# Oraculo_V2.net
KiCad netlist of a schematic drawn in EAGLE
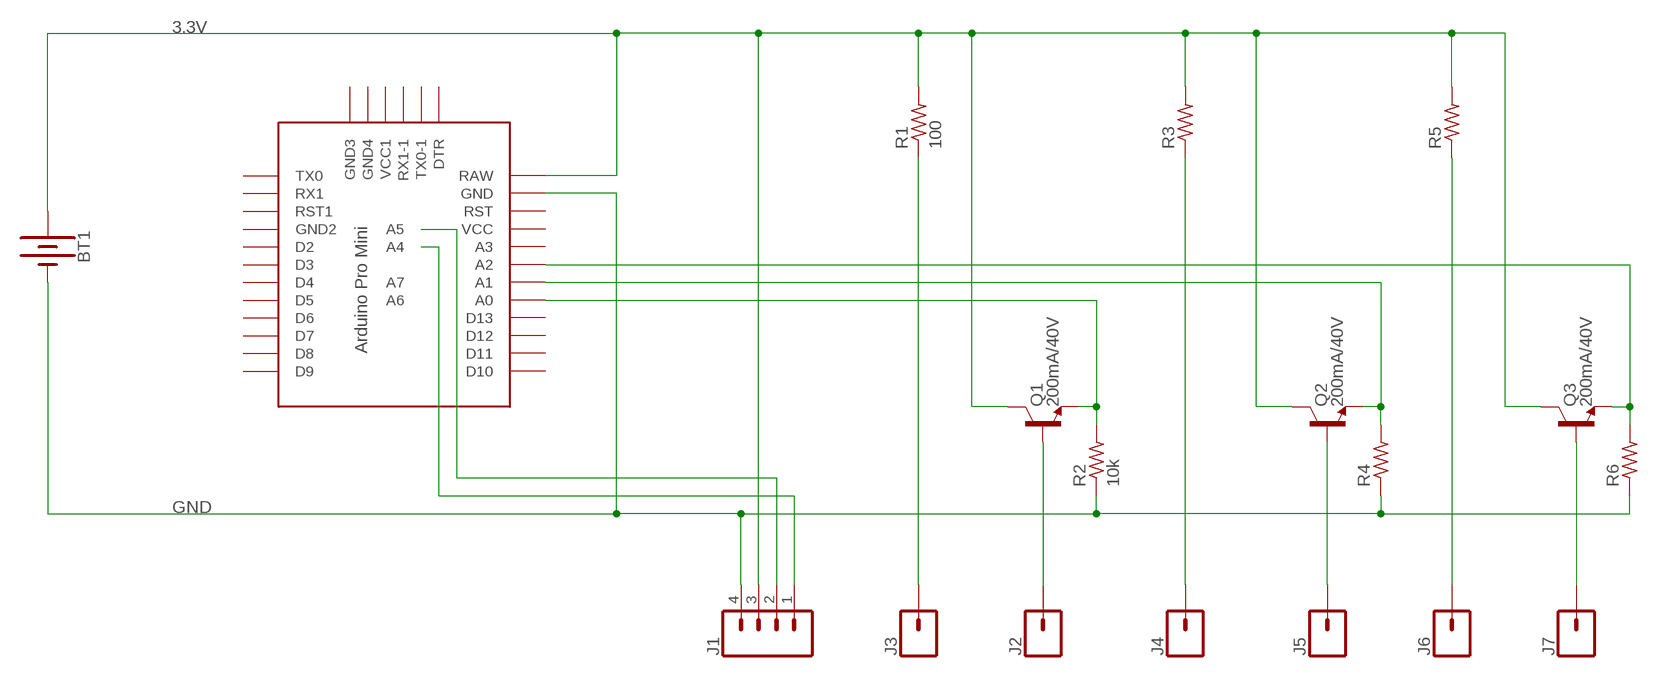
[diagram p0: schematic, sheet 1]

(export (version "E")
  (design (tool "Eeschema 10.0.6"))
  (components
    (comp (ref "BT1")
      (value "BATTERY-20MM_PTH")
      (footprint "eagle-import:BATTCOM_20MM_PTH")
      (libsource (lib "eagle-import") (part "BATTERY-20MM_PTH"))
    )
    (comp (ref "J1")
      (value "CONN_04")
      (footprint "eagle-import:1X04")
      (libsource (lib "eagle-import") (part "CONN_04"))
    )
    (comp (ref "J2")
      (value "CONN_01PTH_2MM")
      (footprint "eagle-import:1X01_2MM")
      (libsource (lib "eagle-import") (part "CONN_01PTH_2MM"))
    )
    (comp (ref "J3")
      (value "CONN_01PTH_2MM")
      (footprint "eagle-import:1X01_2MM")
      (libsource (lib "eagle-import") (part "CONN_01PTH_2MM"))
    )
    (comp (ref "J4")
      (value "CONN_01PTH_2MM")
      (footprint "eagle-import:1X01_2MM")
      (libsource (lib "eagle-import") (part "CONN_01PTH_2MM"))
    )
    (comp (ref "J5")
      (value "CONN_01PTH_2MM")
      (footprint "eagle-import:1X01_2MM")
      (libsource (lib "eagle-import") (part "CONN_01PTH_2MM"))
    )
    (comp (ref "J6")
      (value "CONN_01PTH_2MM")
      (footprint "eagle-import:1X01_2MM")
      (libsource (lib "eagle-import") (part "CONN_01PTH_2MM"))
    )
    (comp (ref "J7")
      (value "CONN_01PTH_2MM")
      (footprint "eagle-import:1X01_2MM")
      (libsource (lib "eagle-import") (part "CONN_01PTH_2MM"))
    )
    (comp (ref "Q1")
      (value "200mA/40V")
      (footprint "eagle-import:TO-92")
      (libsource (lib "eagle-import") (part "TRANS_NPN-2N3904"))
    )
    (comp (ref "Q2")
      (value "200mA/40V")
      (footprint "eagle-import:TO-92")
      (libsource (lib "eagle-import") (part "TRANS_NPN-2N3904"))
    )
    (comp (ref "Q3")
      (value "200mA/40V")
      (footprint "eagle-import:TO-92")
      (libsource (lib "eagle-import") (part "TRANS_NPN-2N3904"))
    )
    (comp (ref "R1")
      (value "100")
      (footprint "eagle-import:0204_7")
      (libsource (lib "eagle-import") (part "R-US_0204/7"))
    )
    (comp (ref "R2")
      (value "10k")
      (footprint "eagle-import:0204_7")
      (libsource (lib "eagle-import") (part "R-US_0204/7"))
    )
    (comp (ref "R3")
      (value "R-US_0204/7")
      (footprint "eagle-import:0204_7")
      (libsource (lib "eagle-import") (part "R-US_0204/7"))
    )
    (comp (ref "R4")
      (value "R-US_0204/7")
      (footprint "eagle-import:0204_7")
      (libsource (lib "eagle-import") (part "R-US_0204/7"))
    )
    (comp (ref "R5")
      (value "R-US_0204/7")
      (footprint "eagle-import:0204_7")
      (libsource (lib "eagle-import") (part "R-US_0204/7"))
    )
    (comp (ref "R6")
      (value "R-US_0204/7")
      (footprint "eagle-import:0204_7")
      (libsource (lib "eagle-import") (part "R-US_0204/7"))
    )
    (comp (ref "U$1")
      (value "PRO-MINI-2")
      (footprint "eagle-import:PRO-MINI-2")
      (libsource (lib "eagle-import") (part "PRO-MINI-2"))
    )
  )
  (nets
    (net (code "1") (name "/3.3V") (class "Default")
      (node (ref "BT1") (pin "1") (pinfunction "+_1") (pintype "power_in"))
      (node (ref "J1") (pin "3") (pinfunction "3_3") (pintype "passive"))
      (node (ref "Q1") (pin "3") (pinfunction "C_3") (pintype "passive"))
      (node (ref "Q2") (pin "3") (pinfunction "C_3") (pintype "passive"))
      (node (ref "Q3") (pin "3") (pinfunction "C_3") (pintype "passive"))
      (node (ref "R1") (pin "2") (pinfunction "2_2") (pintype "passive"))
      (node (ref "R3") (pin "2") (pinfunction "2_2") (pintype "passive"))
      (node (ref "R5") (pin "2") (pinfunction "2_2") (pintype "passive"))
      (node (ref "U$1") (pin "RAW") (pinfunction "RAW_RAW") (pintype "bidirectional"))
    )
    (net (code "2") (name "/GND") (class "Default")
      (node (ref "BT1") (pin "2") (pinfunction "-_2") (pintype "power_in"))
      (node (ref "J1") (pin "4") (pinfunction "4_4") (pintype "passive"))
      (node (ref "R2") (pin "1") (pinfunction "1_1") (pintype "passive"))
      (node (ref "R4") (pin "1") (pinfunction "1_1") (pintype "passive"))
      (node (ref "R6") (pin "1") (pinfunction "1_1") (pintype "passive"))
      (node (ref "U$1") (pin "GND") (pinfunction "GND_GND") (pintype "bidirectional"))
    )
    (net (code "3") (name "Net-(J1-Pad1)") (class "Default")
      (node (ref "J1") (pin "1") (pinfunction "1_1") (pintype "passive"))
      (node (ref "U$1") (pin "A4") (pinfunction "A4_A4") (pintype "bidirectional"))
    )
    (net (code "4") (name "Net-(J1-Pad2)") (class "Default")
      (node (ref "J1") (pin "2") (pinfunction "2_2") (pintype "passive"))
      (node (ref "U$1") (pin "A5") (pinfunction "A5_A5") (pintype "bidirectional"))
    )
    (net (code "5") (name "Net-(J3-Pad1)") (class "Default")
      (node (ref "J3") (pin "1") (pinfunction "1_1") (pintype "passive"))
      (node (ref "R1") (pin "1") (pinfunction "1_1") (pintype "passive"))
    )
    (net (code "6") (name "Net-(J4-Pad1)") (class "Default")
      (node (ref "J4") (pin "1") (pinfunction "1_1") (pintype "passive"))
      (node (ref "R3") (pin "1") (pinfunction "1_1") (pintype "passive"))
    )
    (net (code "7") (name "Net-(J6-Pad1)") (class "Default")
      (node (ref "J6") (pin "1") (pinfunction "1_1") (pintype "passive"))
      (node (ref "R5") (pin "1") (pinfunction "1_1") (pintype "passive"))
    )
    (net (code "8") (name "Net-(Q1-B)") (class "Default")
      (node (ref "J2") (pin "1") (pinfunction "1_1") (pintype "passive"))
      (node (ref "Q1") (pin "2") (pinfunction "B_2") (pintype "passive"))
    )
    (net (code "9") (name "Net-(Q1-E)") (class "Default")
      (node (ref "Q1") (pin "1") (pinfunction "E_1") (pintype "passive"))
      (node (ref "R2") (pin "2") (pinfunction "2_2") (pintype "passive"))
      (node (ref "U$1") (pin "A0") (pinfunction "A0_A0") (pintype "bidirectional"))
    )
    (net (code "10") (name "Net-(Q2-B)") (class "Default")
      (node (ref "J5") (pin "1") (pinfunction "1_1") (pintype "passive"))
      (node (ref "Q2") (pin "2") (pinfunction "B_2") (pintype "passive"))
    )
    (net (code "11") (name "Net-(Q2-E)") (class "Default")
      (node (ref "Q2") (pin "1") (pinfunction "E_1") (pintype "passive"))
      (node (ref "R4") (pin "2") (pinfunction "2_2") (pintype "passive"))
      (node (ref "U$1") (pin "A1") (pinfunction "A1_A1") (pintype "bidirectional"))
    )
    (net (code "12") (name "Net-(Q3-B)") (class "Default")
      (node (ref "J7") (pin "1") (pinfunction "1_1") (pintype "passive"))
      (node (ref "Q3") (pin "2") (pinfunction "B_2") (pintype "passive"))
    )
    (net (code "13") (name "Net-(Q3-E)") (class "Default")
      (node (ref "Q3") (pin "1") (pinfunction "E_1") (pintype "passive"))
      (node (ref "R6") (pin "2") (pinfunction "2_2") (pintype "passive"))
      (node (ref "U$1") (pin "A2") (pinfunction "A2_A2") (pintype "bidirectional"))
    )
    (net (code "14") (name "unconnected-(U$1-GND2-PadGND1)") (class "Default")
      (node (ref "U$1") (pin "GND1") (pinfunction "GND2_GND1") (pintype "bidirectional"))
    )
    (net (code "15") (name "unconnected-(U$1-GND3-PadGND2)") (class "Default")
      (node (ref "U$1") (pin "GND2") (pinfunction "GND3_GND2") (pintype "bidirectional"))
    )
    (net (code "16") (name "unconnected-(U$1-GND4-PadGND3)") (class "Default")
      (node (ref "U$1") (pin "GND3") (pinfunction "GND4_GND3") (pintype "bidirectional"))
    )
    (net (code "17") (name "unconnected-(U$1-PadA3)") (class "Default")
      (node (ref "U$1") (pin "A3") (pinfunction "A3_A3") (pintype "bidirectional"))
    )
    (net (code "18") (name "unconnected-(U$1-PadA6)") (class "Default")
      (node (ref "U$1") (pin "A6") (pinfunction "A6_A6") (pintype "bidirectional"))
    )
    (net (code "19") (name "unconnected-(U$1-PadA7)") (class "Default")
      (node (ref "U$1") (pin "A7") (pinfunction "A7_A7") (pintype "bidirectional"))
    )
    (net (code "20") (name "unconnected-(U$1-PadD2)") (class "Default")
      (node (ref "U$1") (pin "D2") (pinfunction "D2_D2") (pintype "bidirectional"))
    )
    (net (code "21") (name "unconnected-(U$1-PadD3)") (class "Default")
      (node (ref "U$1") (pin "D3") (pinfunction "D3_D3") (pintype "bidirectional"))
    )
    (net (code "22") (name "unconnected-(U$1-PadD4)") (class "Default")
      (node (ref "U$1") (pin "D4") (pinfunction "D4_D4") (pintype "bidirectional"))
    )
    (net (code "23") (name "unconnected-(U$1-PadD5)") (class "Default")
      (node (ref "U$1") (pin "D5") (pinfunction "D5_D5") (pintype "bidirectional"))
    )
    (net (code "24") (name "unconnected-(U$1-PadD6)") (class "Default")
      (node (ref "U$1") (pin "D6") (pinfunction "D6_D6") (pintype "bidirectional"))
    )
    (net (code "25") (name "unconnected-(U$1-PadD7)") (class "Default")
      (node (ref "U$1") (pin "D7") (pinfunction "D7_D7") (pintype "bidirectional"))
    )
    (net (code "26") (name "unconnected-(U$1-PadD8)") (class "Default")
      (node (ref "U$1") (pin "D8") (pinfunction "D8_D8") (pintype "bidirectional"))
    )
    (net (code "27") (name "unconnected-(U$1-PadD9)") (class "Default")
      (node (ref "U$1") (pin "D9") (pinfunction "D9_D9") (pintype "bidirectional"))
    )
    (net (code "28") (name "unconnected-(U$1-PadD10)") (class "Default")
      (node (ref "U$1") (pin "D10") (pinfunction "D10_D10") (pintype "bidirectional"))
    )
    (net (code "29") (name "unconnected-(U$1-PadD11)") (class "Default")
      (node (ref "U$1") (pin "D11") (pinfunction "D11_D11") (pintype "bidirectional"))
    )
    (net (code "30") (name "unconnected-(U$1-PadD12)") (class "Default")
      (node (ref "U$1") (pin "D12") (pinfunction "D12_D12") (pintype "bidirectional"))
    )
    (net (code "31") (name "unconnected-(U$1-PadD13)") (class "Default")
      (node (ref "U$1") (pin "D13") (pinfunction "D13_D13") (pintype "bidirectional"))
    )
    (net (code "32") (name "unconnected-(U$1-PadDTR)") (class "Default")
      (node (ref "U$1") (pin "DTR") (pinfunction "DTR_DTR") (pintype "bidirectional"))
    )
    (net (code "33") (name "unconnected-(U$1-PadRST)") (class "Default")
      (node (ref "U$1") (pin "RST") (pinfunction "RST_RST") (pintype "bidirectional"))
    )
    (net (code "34") (name "unconnected-(U$1-PadRST1)") (class "Default")
      (node (ref "U$1") (pin "RST1") (pinfunction "RST1_RST1") (pintype "bidirectional"))
    )
    (net (code "35") (name "unconnected-(U$1-PadRX1)") (class "Default")
      (node (ref "U$1") (pin "RX1") (pinfunction "RX1_RX1") (pintype "bidirectional"))
    )
    (net (code "36") (name "unconnected-(U$1-PadRX1-1)") (class "Default")
      (node (ref "U$1") (pin "RX1-1") (pinfunction "RX1-1_RX1-1") (pintype "bidirectional"))
    )
    (net (code "37") (name "unconnected-(U$1-PadTX0)") (class "Default")
      (node (ref "U$1") (pin "TX0") (pinfunction "TX0_TX0") (pintype "bidirectional"))
    )
    (net (code "38") (name "unconnected-(U$1-PadTX0-1)") (class "Default")
      (node (ref "U$1") (pin "TX0-1") (pinfunction "TX0-1_TX0-1") (pintype "bidirectional"))
    )
    (net (code "39") (name "unconnected-(U$1-PadVCC)") (class "Default")
      (node (ref "U$1") (pin "VCC") (pinfunction "VCC_VCC") (pintype "bidirectional"))
    )
    (net (code "40") (name "unconnected-(U$1-PadVCC1)") (class "Default")
      (node (ref "U$1") (pin "VCC1") (pinfunction "VCC1_VCC1") (pintype "bidirectional"))
    )
  )
)
